# crc.net
KiCad netlist of a schematic drawn in EAGLE
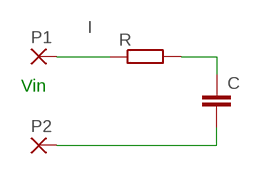
[diagram p0: schematic, sheet 1]

(export (version "E")
  (design (tool "Eeschema 10.0.6"))
  (components
    (comp (ref "C")
      (value "C5/3")
      (footprint "eagle-import:C5B3")
      (libsource (lib "eagle-import") (part "C5/3"))
    )
    (comp (ref "P1")
      (value "2,54/1,0")
      (footprint "eagle-import:2,54_1,0")
      (libsource (lib "eagle-import") (part "2,54/1,0"))
    )
    (comp (ref "P2")
      (value "2,54/1,0")
      (footprint "eagle-import:2,54_1,0")
      (libsource (lib "eagle-import") (part "2,54/1,0"))
    )
    (comp (ref "R")
      (value "R-EU_0207/5V")
      (footprint "eagle-import:0207_5V")
      (libsource (lib "eagle-import") (part "R-EU_0207/5V"))
    )
  )
  (nets
    (net (code "1") (name "/I") (class "Default")
      (node (ref "P1") (pin "1") (pinfunction "P_1") (pintype "passive"))
      (node (ref "R") (pin "1") (pinfunction "1_1") (pintype "passive"))
    )
    (net (code "2") (name "Net-(C-Pad1)") (class "Default")
      (node (ref "C") (pin "1") (pinfunction "1_1") (pintype "passive"))
      (node (ref "R") (pin "2") (pinfunction "2_2") (pintype "passive"))
    )
    (net (code "3") (name "Net-(P2-P)") (class "Default")
      (node (ref "C") (pin "2") (pinfunction "2_2") (pintype "passive"))
      (node (ref "P2") (pin "1") (pinfunction "P_1") (pintype "passive"))
    )
  )
)
